# FLEXQCMV2_2.net
KiCad netlist of a schematic drawn in EAGLE
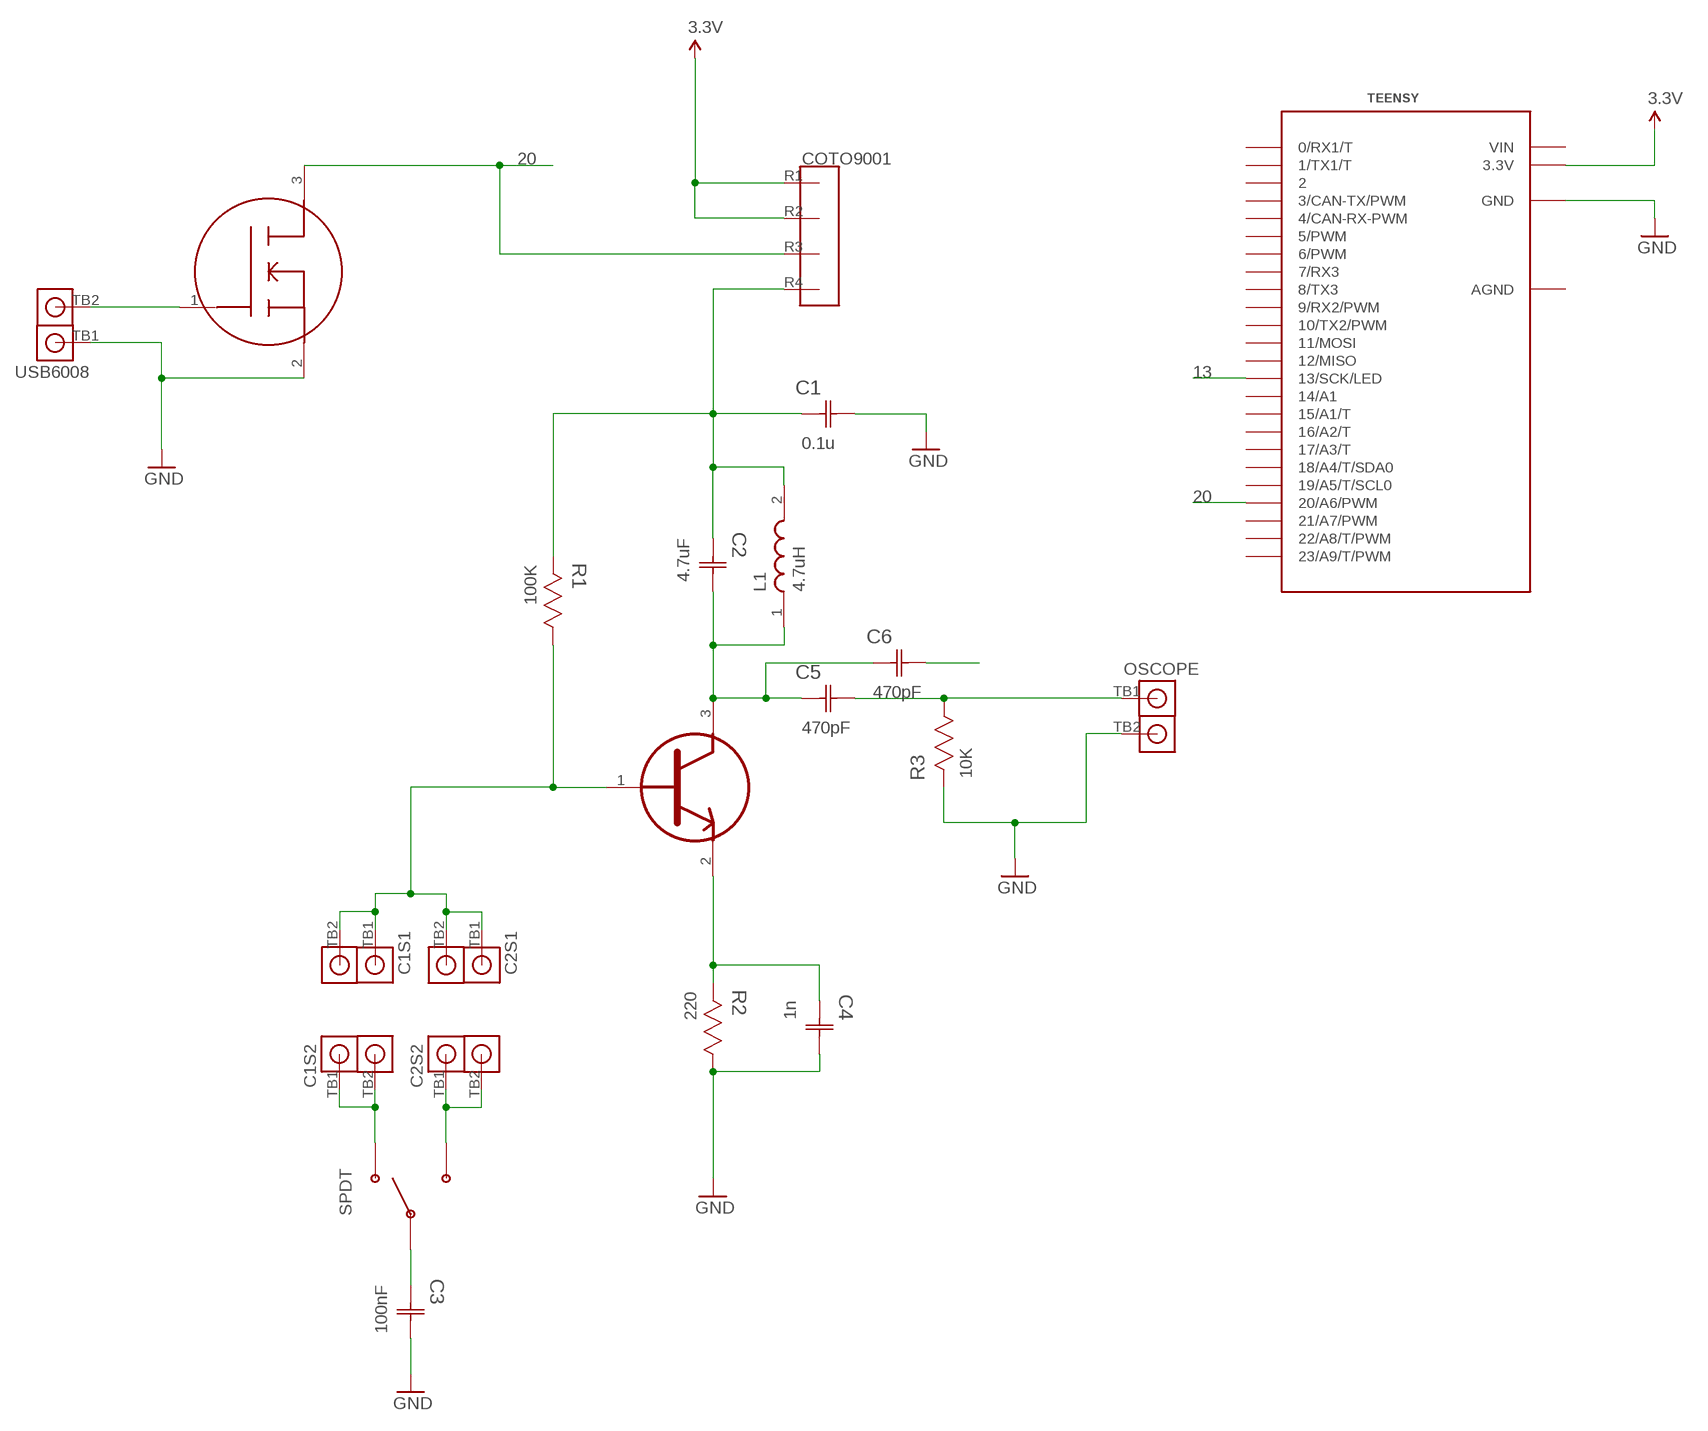
[diagram p0: schematic, sheet 1]

(export (version "E")
  (design (tool "Eeschema 10.0.6"))
  (components
    (comp (ref "C1")
      (value "0.1u")
      (footprint "eagle-import:CAPC3216X88N")
      (fields (field (name "MPN") "C1206C104K1RACTU") (field (name "TOLERANCE") "±10%"))
      (libsource (lib "eagle-import") (part "C1206C104K1RACTU"))
    )
    (comp (ref "C1S1")
      (value "TERMBLOCKX2")
      (footprint "eagle-import:TERMBLOCKX2")
      (libsource (lib "eagle-import") (part "TERMBLOCKX2"))
    )
    (comp (ref "C1S2")
      (value "TERMBLOCKX2")
      (footprint "eagle-import:TERMBLOCKX2")
      (libsource (lib "eagle-import") (part "TERMBLOCKX2"))
    )
    (comp (ref "C2")
      (value "4.7uF")
      (footprint "eagle-import:CAPC3216X180N")
      (fields (field (name "MPN") "C1206C475K3RACTU") (field (name "TOLERANCE") "±10%"))
      (libsource (lib "eagle-import") (part "C1206C475K3RACTU"))
    )
    (comp (ref "C2S1")
      (value "TERMBLOCKX2")
      (footprint "eagle-import:TERMBLOCKX2")
      (libsource (lib "eagle-import") (part "TERMBLOCKX2"))
    )
    (comp (ref "C2S2")
      (value "TERMBLOCKX2")
      (footprint "eagle-import:TERMBLOCKX2")
      (libsource (lib "eagle-import") (part "TERMBLOCKX2"))
    )
    (comp (ref "C3")
      (value "100nF")
      (footprint "eagle-import:CAPC3216X88N")
      (fields (field (name "MPN") "C1206C104K1RACTU") (field (name "TOLERANCE") "±10%"))
      (libsource (lib "eagle-import") (part "C1206C104K1RACTU"))
    )
    (comp (ref "C4")
      (value "1n")
      (footprint "eagle-import:CAPC3216X88N")
      (fields (field (name "MPN") "C1206C103K5RACTU") (field (name "TOLERANCE") "±10%"))
      (libsource (lib "eagle-import") (part "C1206C103K5RACTU"))
    )
    (comp (ref "C5")
      (value "470pF")
      (footprint "eagle-import:CAPC3216X100N")
      (fields (field (name "MPN") "C1206C474K3RACTU") (field (name "TOLERANCE") "±10%"))
      (libsource (lib "eagle-import") (part "C1206C474K3RACTU"))
    )
    (comp (ref "C6")
      (value "470pF")
      (footprint "eagle-import:CAPC3216X100N")
      (fields (field (name "MPN") "C1206C474K3RACTU") (field (name "TOLERANCE") "±10%"))
      (libsource (lib "eagle-import") (part "C1206C474K3RACTU"))
    )
    (comp (ref "COTO9001")
      (value "COTO9001")
      (footprint "eagle-import:COTO9001")
      (libsource (lib "eagle-import") (part "COTO9001"))
    )
    (comp (ref "L1")
      (value "4.7uH")
      (footprint "eagle-import:INDC3225X210N")
      (fields (field (name "MPN") "B82422A1472K100") (field (name "TOLERANCE") "±10%"))
      (libsource (lib "eagle-import") (part "B82422A1472K100"))
    )
    (comp (ref "OSCOPE")
      (value "TERMBLOCKX2")
      (footprint "eagle-import:TERMBLOCKX2")
      (libsource (lib "eagle-import") (part "TERMBLOCKX2"))
    )
    (comp (ref "R1")
      (value "100K")
      (footprint "eagle-import:RESC3216X71N")
      (fields (field (name "MPN") "CRCW1206100KJNEA") (field (name "TOLERANCE") "±5%"))
      (libsource (lib "eagle-import") (part "CRCW1206100KJNEA"))
    )
    (comp (ref "R2")
      (value "220")
      (footprint "eagle-import:RESC3216X71N")
      (fields (field (name "MPN") "CRCW1206220RJNEA") (field (name "TOLERANCE") "±5%"))
      (libsource (lib "eagle-import") (part "CRCW1206220RJNEA"))
    )
    (comp (ref "R3")
      (value "10K")
      (footprint "eagle-import:RESC3216X71N")
      (fields (field (name "MPN") "CRCW120610K0FKEA") (field (name "TOLERANCE") "±1%"))
      (libsource (lib "eagle-import") (part "CRCW120610K0FKEA"))
    )
    (comp (ref "SPDT")
      (value "SPDTSWITCH")
      (footprint "eagle-import:SPDTSWITCH")
      (libsource (lib "eagle-import") (part "SPDTSWITCH"))
    )
    (comp (ref "TEENSY")
      (value "TEENSY_3.1_DIL")
      (footprint "eagle-import:TEENSY3-DIL")
      (libsource (lib "eagle-import") (part "TEENSY_3.1_DIL"))
    )
    (comp (ref "U1")
      (value "FET")
      (footprint "eagle-import:SOT95P230X110-3N")
      (fields (field (name "MPN") "2N7002K"))
      (libsource (lib "eagle-import") (part "2N7002K"))
    )
    (comp (ref "U2")
      (value "BJT")
      (footprint "eagle-import:SOT95P230X110-3N")
      (libsource (lib "eagle-import") (part "BC847C"))
    )
    (comp (ref "USB6008")
      (value "TERMBLOCKX2")
      (footprint "eagle-import:TERMBLOCKX2")
      (libsource (lib "eagle-import") (part "TERMBLOCKX2"))
    )
  )
  (nets
    (net (code "1") (name "/13") (class "Default")
      (node (ref "C6") (pin "2") (pinfunction "C2_2") (pintype "passive"))
      (node (ref "TEENSY") (pin "13") (pinfunction "13/SCK/LED_13") (pintype "bidirectional"))
    )
    (net (code "2") (name "/20") (class "Default")
      (node (ref "COTO9001") (pin "R3") (pinfunction "R3_R3") (pintype "bidirectional"))
      (node (ref "TEENSY") (pin "20/A6") (pinfunction "20/A6/PWM_20/A6") (pintype "bidirectional"))
      (node (ref "U1") (pin "3") (pinfunction "D_3") (pintype "bidirectional"))
    )
    (net (code "3") (name "/AGND") (class "Default")
      (node (ref "TEENSY") (pin "AGND") (pinfunction "AGND_AGND") (pintype "power_in"))
    )
    (net (code "4") (name "/VIN") (class "Default")
      (node (ref "TEENSY") (pin "VIN") (pinfunction "VIN_VIN") (pintype "power_in"))
    )
    (net (code "5") (name "3.3V") (class "Default")
      (node (ref "COTO9001") (pin "R1") (pinfunction "R1_R1") (pintype "bidirectional"))
      (node (ref "COTO9001") (pin "R2") (pinfunction "R2_R2") (pintype "bidirectional"))
      (node (ref "TEENSY") (pin "3.3V") (pinfunction "3.3V_3.3V") (pintype "power_in"))
    )
    (net (code "6") (name "GND") (class "Default")
      (node (ref "C1") (pin "2") (pinfunction "C2_2") (pintype "passive"))
      (node (ref "C3") (pin "2") (pinfunction "C2_2") (pintype "passive"))
      (node (ref "C4") (pin "2") (pinfunction "C2_2") (pintype "passive"))
      (node (ref "OSCOPE") (pin "TB2") (pinfunction "TB2_TB2") (pintype "bidirectional"))
      (node (ref "R2") (pin "1") (pinfunction "1_1") (pintype "passive"))
      (node (ref "R3") (pin "2") (pinfunction "2_2") (pintype "passive"))
      (node (ref "TEENSY") (pin "GND") (pinfunction "GND_GND") (pintype "power_in"))
      (node (ref "U1") (pin "2") (pinfunction "S_2") (pintype "bidirectional"))
      (node (ref "USB6008") (pin "TB1") (pinfunction "TB1_TB1") (pintype "bidirectional"))
    )
    (net (code "7") (name "Net-(C1-C1)") (class "Default")
      (node (ref "C1") (pin "1") (pinfunction "C1_1") (pintype "passive"))
      (node (ref "C2") (pin "1") (pinfunction "C1_1") (pintype "passive"))
      (node (ref "COTO9001") (pin "R4") (pinfunction "R4_R4") (pintype "bidirectional"))
      (node (ref "L1") (pin "2") (pinfunction "P$2_2") (pintype "bidirectional"))
      (node (ref "R1") (pin "2") (pinfunction "2_2") (pintype "passive"))
    )
    (net (code "8") (name "Net-(C1S2-PadTB1)") (class "Default")
      (node (ref "C1S2") (pin "TB1") (pinfunction "TB1_TB1") (pintype "bidirectional"))
      (node (ref "C1S2") (pin "TB2") (pinfunction "TB2_TB2") (pintype "bidirectional"))
      (node (ref "SPDT") (pin "SW1") (pinfunction "SW1_SW1") (pintype "bidirectional"))
    )
    (net (code "9") (name "Net-(C2-C2)") (class "Default")
      (node (ref "C2") (pin "2") (pinfunction "C2_2") (pintype "passive"))
      (node (ref "C5") (pin "1") (pinfunction "C1_1") (pintype "passive"))
      (node (ref "C6") (pin "1") (pinfunction "C1_1") (pintype "passive"))
      (node (ref "L1") (pin "1") (pinfunction "P$1_1") (pintype "bidirectional"))
      (node (ref "U2") (pin "3") (pinfunction "C_3") (pintype "bidirectional"))
    )
    (net (code "10") (name "Net-(C2S2-PadTB1)") (class "Default")
      (node (ref "C2S2") (pin "TB1") (pinfunction "TB1_TB1") (pintype "bidirectional"))
      (node (ref "C2S2") (pin "TB2") (pinfunction "TB2_TB2") (pintype "bidirectional"))
      (node (ref "SPDT") (pin "SW3") (pinfunction "SW3_SW3") (pintype "bidirectional"))
    )
    (net (code "11") (name "Net-(C3-C1)") (class "Default")
      (node (ref "C3") (pin "1") (pinfunction "C1_1") (pintype "passive"))
      (node (ref "SPDT") (pin "SW2") (pinfunction "SW2_SW2") (pintype "bidirectional"))
    )
    (net (code "12") (name "Net-(C4-C1)") (class "Default")
      (node (ref "C4") (pin "1") (pinfunction "C1_1") (pintype "passive"))
      (node (ref "R2") (pin "2") (pinfunction "2_2") (pintype "passive"))
      (node (ref "U2") (pin "2") (pinfunction "E_2") (pintype "bidirectional"))
    )
    (net (code "13") (name "Net-(C5-C2)") (class "Default")
      (node (ref "C5") (pin "2") (pinfunction "C2_2") (pintype "passive"))
      (node (ref "OSCOPE") (pin "TB1") (pinfunction "TB1_TB1") (pintype "bidirectional"))
      (node (ref "R3") (pin "1") (pinfunction "1_1") (pintype "passive"))
    )
    (net (code "14") (name "Net-(U1-G)") (class "Default")
      (node (ref "U1") (pin "1") (pinfunction "G_1") (pintype "bidirectional"))
      (node (ref "USB6008") (pin "TB2") (pinfunction "TB2_TB2") (pintype "bidirectional"))
    )
    (net (code "15") (name "Net-(U2-B)") (class "Default")
      (node (ref "C1S1") (pin "TB1") (pinfunction "TB1_TB1") (pintype "bidirectional"))
      (node (ref "C1S1") (pin "TB2") (pinfunction "TB2_TB2") (pintype "bidirectional"))
      (node (ref "C2S1") (pin "TB1") (pinfunction "TB1_TB1") (pintype "bidirectional"))
      (node (ref "C2S1") (pin "TB2") (pinfunction "TB2_TB2") (pintype "bidirectional"))
      (node (ref "R1") (pin "1") (pinfunction "1_1") (pintype "passive"))
      (node (ref "U2") (pin "1") (pinfunction "B_1") (pintype "bidirectional"))
    )
    (net (code "16") (name "unconnected-(TEENSY-0{slash}RX1{slash}T-Pad0)") (class "Default")
      (node (ref "TEENSY") (pin "0") (pinfunction "0/RX1/T_0") (pintype "bidirectional"))
    )
    (net (code "17") (name "unconnected-(TEENSY-1{slash}TX1{slash}T-Pad1)") (class "Default")
      (node (ref "TEENSY") (pin "1") (pinfunction "1/TX1/T_1") (pintype "bidirectional"))
    )
    (net (code "18") (name "unconnected-(TEENSY-3{slash}CAN-TX{slash}PWM-Pad3)") (class "Default")
      (node (ref "TEENSY") (pin "3") (pinfunction "3/CAN-TX/PWM_3") (pintype "bidirectional"))
    )
    (net (code "19") (name "unconnected-(TEENSY-4{slash}CAN-RX-PWM-Pad4)") (class "Default")
      (node (ref "TEENSY") (pin "4") (pinfunction "4/CAN-RX-PWM_4") (pintype "bidirectional"))
    )
    (net (code "20") (name "unconnected-(TEENSY-5{slash}PWM-Pad5)") (class "Default")
      (node (ref "TEENSY") (pin "5") (pinfunction "5/PWM_5") (pintype "bidirectional"))
    )
    (net (code "21") (name "unconnected-(TEENSY-6{slash}PWM-Pad6)") (class "Default")
      (node (ref "TEENSY") (pin "6") (pinfunction "6/PWM_6") (pintype "bidirectional"))
    )
    (net (code "22") (name "unconnected-(TEENSY-7{slash}RX3-Pad7)") (class "Default")
      (node (ref "TEENSY") (pin "7") (pinfunction "7/RX3_7") (pintype "bidirectional"))
    )
    (net (code "23") (name "unconnected-(TEENSY-8{slash}TX3-Pad8)") (class "Default")
      (node (ref "TEENSY") (pin "8") (pinfunction "8/TX3_8") (pintype "bidirectional"))
    )
    (net (code "24") (name "unconnected-(TEENSY-9{slash}RX2{slash}PWM-Pad9)") (class "Default")
      (node (ref "TEENSY") (pin "9") (pinfunction "9/RX2/PWM_9") (pintype "bidirectional"))
    )
    (net (code "25") (name "unconnected-(TEENSY-10{slash}TX2{slash}PWM-Pad10)") (class "Default")
      (node (ref "TEENSY") (pin "10") (pinfunction "10/TX2/PWM_10") (pintype "bidirectional"))
    )
    (net (code "26") (name "unconnected-(TEENSY-11{slash}MOSI-Pad11)") (class "Default")
      (node (ref "TEENSY") (pin "11") (pinfunction "11/MOSI_11") (pintype "bidirectional"))
    )
    (net (code "27") (name "unconnected-(TEENSY-12{slash}MISO-Pad12)") (class "Default")
      (node (ref "TEENSY") (pin "12") (pinfunction "12/MISO_12") (pintype "bidirectional"))
    )
    (net (code "28") (name "unconnected-(TEENSY-14{slash}A1-Pad14{slash}A0)") (class "Default")
      (node (ref "TEENSY") (pin "14/A0") (pinfunction "14/A1_14/A0") (pintype "bidirectional"))
    )
    (net (code "29") (name "unconnected-(TEENSY-15{slash}A1{slash}T-Pad15{slash}A1)") (class "Default")
      (node (ref "TEENSY") (pin "15/A1") (pinfunction "15/A1/T_15/A1") (pintype "bidirectional"))
    )
    (net (code "30") (name "unconnected-(TEENSY-16{slash}A2{slash}T-Pad16{slash}A2)") (class "Default")
      (node (ref "TEENSY") (pin "16/A2") (pinfunction "16/A2/T_16/A2") (pintype "bidirectional"))
    )
    (net (code "31") (name "unconnected-(TEENSY-17{slash}A3{slash}T-Pad17{slash}A3)") (class "Default")
      (node (ref "TEENSY") (pin "17/A3") (pinfunction "17/A3/T_17/A3") (pintype "bidirectional"))
    )
    (net (code "32") (name "unconnected-(TEENSY-18{slash}A4{slash}T{slash}SDA0-Pad18{slash}A4)") (class "Default")
      (node (ref "TEENSY") (pin "18/A4") (pinfunction "18/A4/T/SDA0_18/A4") (pintype "bidirectional"))
    )
    (net (code "33") (name "unconnected-(TEENSY-19{slash}A5{slash}T{slash}SCL0-Pad19{slash}A5)") (class "Default")
      (node (ref "TEENSY") (pin "19/A5") (pinfunction "19/A5/T/SCL0_19/A5") (pintype "bidirectional"))
    )
    (net (code "34") (name "unconnected-(TEENSY-21{slash}A7{slash}PWM-Pad21{slash}A7)") (class "Default")
      (node (ref "TEENSY") (pin "21/A7") (pinfunction "21/A7/PWM_21/A7") (pintype "bidirectional"))
    )
    (net (code "35") (name "unconnected-(TEENSY-22{slash}A8{slash}T{slash}PWM-Pad22{slash}A8)") (class "Default")
      (node (ref "TEENSY") (pin "22/A8") (pinfunction "22/A8/T/PWM_22/A8") (pintype "bidirectional"))
    )
    (net (code "36") (name "unconnected-(TEENSY-23{slash}A9{slash}T{slash}PWM-Pad23{slash}A9)") (class "Default")
      (node (ref "TEENSY") (pin "23/A9") (pinfunction "23/A9/T/PWM_23/A9") (pintype "bidirectional"))
    )
    (net (code "37") (name "unconnected-(TEENSY-Pad2)") (class "Default")
      (node (ref "TEENSY") (pin "2") (pinfunction "2_2") (pintype "bidirectional"))
    )
  )
)
